# USB_OTG.net
KiCad netlist of a schematic drawn in Altium Designer
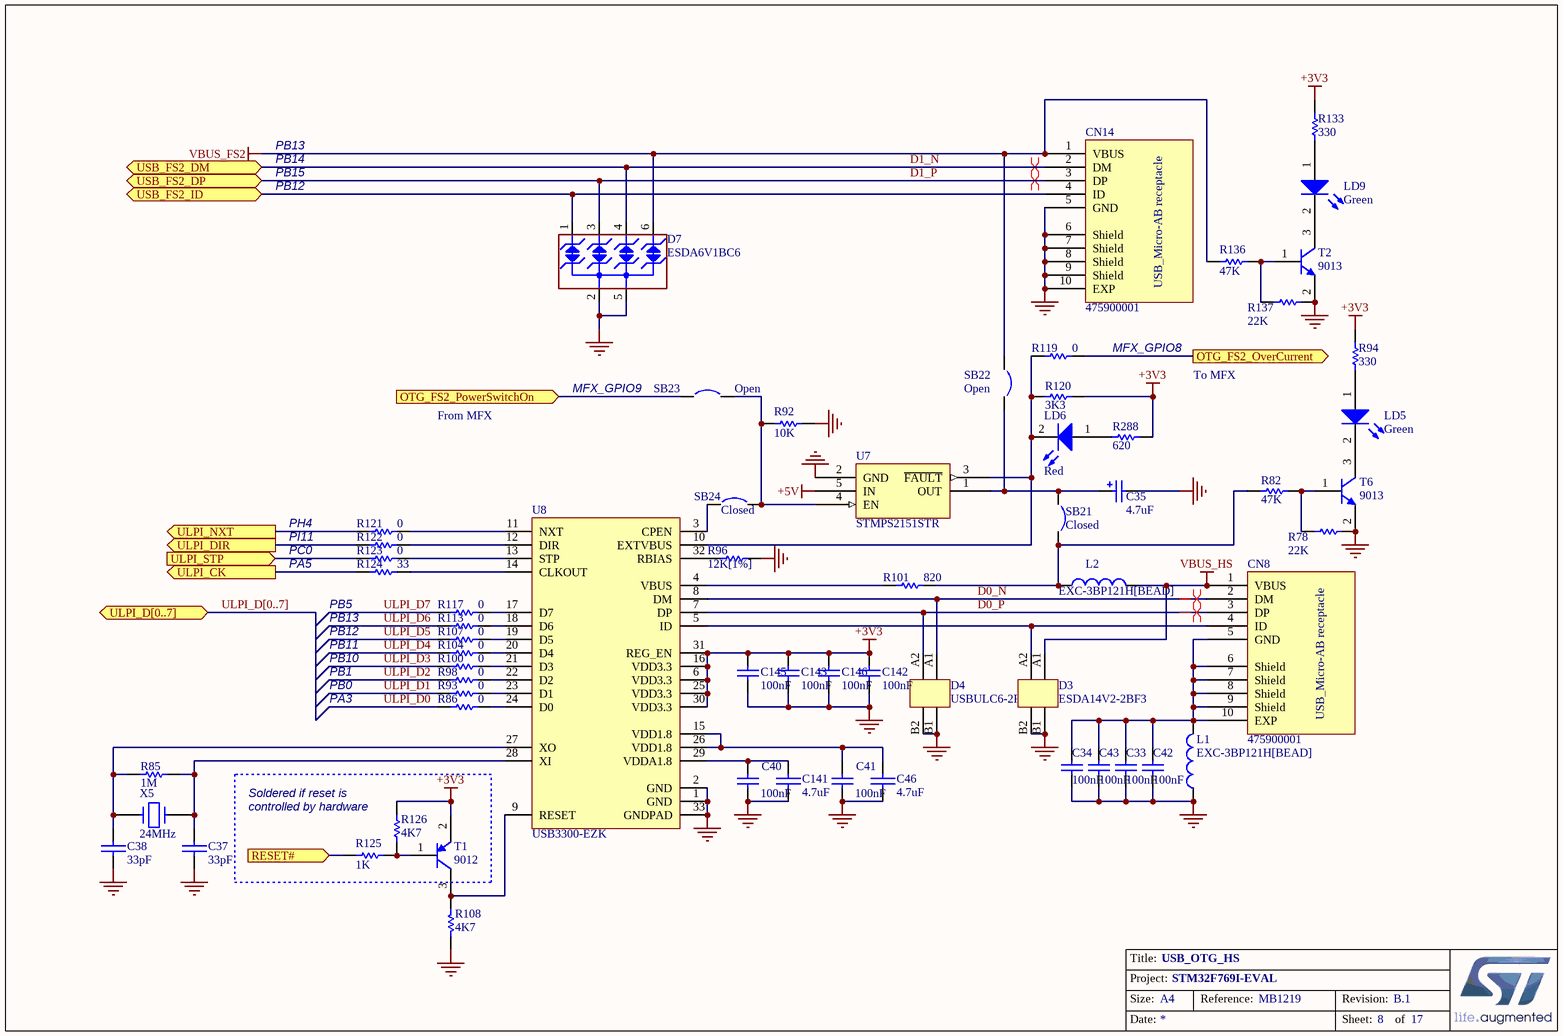
[diagram p0: USB_OTG.SchDoc]

(export (version "E")
  (design (tool "Eeschema 10.0.6"))
  (components
    (comp (ref "C33")
      (value "100nF")
      (footprint "0603C")
      (description "Capacitor")
      (fields (field (name "PUBLISHER") "Altium Limited"))
      (libsource (lib "Miscellaneous Devices") (part "Cap"))
    )
    (comp (ref "C34")
      (value "100nF")
      (footprint "0603C")
      (description "Capacitor")
      (fields (field (name "PUBLISHER") "Altium Limited"))
      (libsource (lib "Miscellaneous Devices") (part "Cap"))
    )
    (comp (ref "C35")
      (value "4.7uF")
      (footprint "TAN-A")
      (description "Polarized Capacitor (Radial)")
      (fields (field (name "PUBLISHER") "Altium Limited"))
      (libsource (lib "Miscellaneous Devices") (part "Cap Pol1"))
    )
    (comp (ref "C37")
      (value "33pF")
      (footprint "0603C")
      (description "Capacitor")
      (libsource (lib "*") (part "CAP"))
    )
    (comp (ref "C38")
      (value "33pF")
      (footprint "0603C")
      (description "Capacitor")
      (libsource (lib "*") (part "CAP"))
    )
    (comp (ref "C40")
      (value "100nF")
      (footprint "0603C")
      (description "Capacitor")
      (fields (field (name "PUBLISHER") "Altium Limited"))
      (libsource (lib "Miscellaneous Devices") (part "Cap"))
    )
    (comp (ref "C41")
      (value "100nF")
      (footprint "0603C")
      (description "Capacitor")
      (fields (field (name "PUBLISHER") "Altium Limited"))
      (libsource (lib "Miscellaneous Devices") (part "Cap"))
    )
    (comp (ref "C42")
      (value "100nF")
      (footprint "0603C")
      (description "Capacitor")
      (fields (field (name "PUBLISHER") "Altium Limited"))
      (libsource (lib "Miscellaneous Devices") (part "Cap"))
    )
    (comp (ref "C43")
      (value "100nF")
      (footprint "0603C")
      (description "Capacitor")
      (fields (field (name "PUBLISHER") "Altium Limited"))
      (libsource (lib "Miscellaneous Devices") (part "Cap"))
    )
    (comp (ref "C46")
      (value "4.7uF")
      (footprint "TAN-A")
      (description "Capacitor")
      (libsource (lib "") (part "CAP_1"))
    )
    (comp (ref "C141")
      (value "4.7uF")
      (footprint "TAN-A")
      (description "Capacitor")
      (libsource (lib "") (part "CAP_1"))
    )
    (comp (ref "C142")
      (value "100nF")
      (footprint "0603C")
      (description "Capacitor")
      (fields (field (name "PUBLISHER") "Altium Limited"))
      (libsource (lib "Miscellaneous Devices") (part "Cap"))
    )
    (comp (ref "C143")
      (value "100nF")
      (footprint "0603C")
      (description "Capacitor")
      (fields (field (name "PUBLISHER") "Altium Limited"))
      (libsource (lib "Miscellaneous Devices") (part "Cap"))
    )
    (comp (ref "C145")
      (value "100nF")
      (footprint "0603C")
      (description "Capacitor")
      (fields (field (name "PUBLISHER") "Altium Limited"))
      (libsource (lib "Miscellaneous Devices") (part "Cap"))
    )
    (comp (ref "C146")
      (value "100nF")
      (footprint "0603C")
      (description "Capacitor")
      (fields (field (name "PUBLISHER") "Altium Limited"))
      (libsource (lib "Miscellaneous Devices") (part "Cap"))
    )
    (comp (ref "CN8")
      (value "475900001")
      (footprint "MOLEX_47590001")
      (libsource (lib "mb1045") (part "475900001"))
    )
    (comp (ref "CN14")
      (value "475900001")
      (footprint "MOLEX_47590001")
      (libsource (lib "mb1045") (part "475900001"))
    )
    (comp (ref "D3")
      (value "ESDA14V2-2BF3")
      (footprint "BGA4_0R4_0R8X0R8")
      (libsource (lib "MB786") (part "ESDA14V2-2BF3"))
    )
    (comp (ref "D4")
      (value "USBULC6-2F3")
      (footprint "BGA4_0R4_1X1")
      (libsource (lib "MB786") (part "USBULC6-2F3"))
    )
    (comp (ref "D7")
      (value "ESDA6V1BC6")
      (footprint "SOT23-6")
      (description "Dual Transil array for ESD protection")
      (libsource (lib "MB1137") (part "ESDA6V1BC6"))
    )
    (comp (ref "L1")
      (value "EXC-3BP121H[BEAD]")
      (footprint "0603L")
      (description "Inductor")
      (fields (field (name "PUBLISHER") "Altium Limited"))
      (libsource (lib "Miscellaneous Devices") (part "Inductor"))
    )
    (comp (ref "L2")
      (value "EXC-3BP121H[BEAD]")
      (footprint "0603L")
      (description "Inductor")
      (fields (field (name "PUBLISHER") "Altium Limited"))
      (libsource (lib "Miscellaneous Devices") (part "Inductor"))
    )
    (comp (ref "LD5")
      (value "Green")
      (footprint "0603D")
      (description "Typical RED, GREEN, YELLOW, AMBER GaAs LED")
      (fields (field (name "PUBLISHER") "Altium Limited"))
      (libsource (lib "Miscellaneous Devices") (part "LED2"))
    )
    (comp (ref "LD6")
      (value "Red")
      (footprint "0603D")
      (description "Typical RED, GREEN, YELLOW, AMBER GaAs LED")
      (fields (field (name "PUBLISHER") "Altium Limited"))
      (libsource (lib "Miscellaneous Devices") (part "LED2"))
    )
    (comp (ref "LD9")
      (value "Green")
      (footprint "0603D")
      (description "Typical RED, GREEN, YELLOW, AMBER GaAs LED")
      (fields (field (name "PUBLISHER") "Altium Limited"))
      (libsource (lib "Miscellaneous Devices") (part "LED2"))
    )
    (comp (ref "R78")
      (value "22K")
      (footprint "0603R")
      (description "Resistor")
      (fields (field (name "PUBLISHER") "Altium Limited"))
      (libsource (lib "Miscellaneous Devices") (part "res1"))
    )
    (comp (ref "R82")
      (value "47K")
      (footprint "0603R")
      (description "Resistor")
      (fields (field (name "PUBLISHER") "Altium Limited"))
      (libsource (lib "Miscellaneous Devices") (part "res1"))
    )
    (comp (ref "R85")
      (value "1M")
      (footprint "0603R")
      (description "Resistor")
      (fields (field (name "PUBLISHER") "Altium Limited"))
      (libsource (lib "Miscellaneous Devices") (part "Res1"))
    )
    (comp (ref "R86")
      (value "0")
      (footprint "0603R")
      (description "Resistor")
      (fields (field (name "PUBLISHER") "Altium Limited"))
      (libsource (lib "Miscellaneous Devices") (part "Res1"))
    )
    (comp (ref "R92")
      (value "10K")
      (footprint "0603R")
      (description "Resistor")
      (fields (field (name "PUBLISHER") "Altium Limited"))
      (libsource (lib "Miscellaneous Devices") (part "res1"))
    )
    (comp (ref "R93")
      (value "0")
      (footprint "0603R")
      (description "Resistor")
      (fields (field (name "PUBLISHER") "Altium Limited"))
      (libsource (lib "Miscellaneous Devices") (part "Res1"))
    )
    (comp (ref "R94")
      (value "330")
      (footprint "0603R")
      (description "Resistor")
      (fields (field (name "PUBLISHER") "Altium Limited"))
      (libsource (lib "Miscellaneous Devices") (part "res1"))
    )
    (comp (ref "R96")
      (value "12K[1%]")
      (footprint "0603R")
      (description "Resistor")
      (fields (field (name "PUBLISHER") "Altium Limited"))
      (libsource (lib "Miscellaneous Devices") (part "Res1"))
    )
    (comp (ref "R98")
      (value "0")
      (footprint "0603R")
      (description "Resistor")
      (fields (field (name "PUBLISHER") "Altium Limited"))
      (libsource (lib "Miscellaneous Devices") (part "Res1"))
    )
    (comp (ref "R100")
      (value "0")
      (footprint "0603R")
      (description "Resistor")
      (fields (field (name "PUBLISHER") "Altium Limited"))
      (libsource (lib "Miscellaneous Devices") (part "Res1"))
    )
    (comp (ref "R101")
      (value "820")
      (footprint "0603R")
      (description "Resistor")
      (fields (field (name "PUBLISHER") "Altium Limited"))
      (libsource (lib "Miscellaneous Devices") (part "res1"))
    )
    (comp (ref "R104")
      (value "0")
      (footprint "0603R")
      (description "Resistor")
      (fields (field (name "PUBLISHER") "Altium Limited"))
      (libsource (lib "Miscellaneous Devices") (part "Res1"))
    )
    (comp (ref "R107")
      (value "0")
      (footprint "0603R")
      (description "Resistor")
      (fields (field (name "PUBLISHER") "Altium Limited"))
      (libsource (lib "Miscellaneous Devices") (part "Res1"))
    )
    (comp (ref "R108")
      (value "4K7")
      (footprint "0603R")
      (description "Resistor")
      (fields (field (name "PUBLISHER") "Altium Limited"))
      (libsource (lib "*") (part "Res1"))
    )
    (comp (ref "R113")
      (value "0")
      (footprint "0603R")
      (description "Resistor")
      (fields (field (name "PUBLISHER") "Altium Limited"))
      (libsource (lib "Miscellaneous Devices") (part "Res1"))
    )
    (comp (ref "R117")
      (value "0")
      (footprint "0603R")
      (description "Resistor")
      (fields (field (name "PUBLISHER") "Altium Limited"))
      (libsource (lib "Miscellaneous Devices") (part "Res1"))
    )
    (comp (ref "R119")
      (value "0")
      (footprint "0603R")
      (description "Resistor")
      (fields (field (name "PUBLISHER") "Altium Limited"))
      (libsource (lib "Miscellaneous Devices") (part "Res1"))
    )
    (comp (ref "R120")
      (value "3K3")
      (footprint "0603R")
      (description "Resistor")
      (fields (field (name "PUBLISHER") "Altium Limited"))
      (libsource (lib "Miscellaneous Devices") (part "res1"))
    )
    (comp (ref "R121")
      (value "0")
      (footprint "0603R")
      (description "Resistor")
      (fields (field (name "PUBLISHER") "Altium Limited"))
      (libsource (lib "Miscellaneous Devices") (part "Res1"))
    )
    (comp (ref "R122")
      (value "0")
      (footprint "0603R")
      (description "Resistor")
      (fields (field (name "PUBLISHER") "Altium Limited"))
      (libsource (lib "Miscellaneous Devices") (part "Res1"))
    )
    (comp (ref "R123")
      (value "0")
      (footprint "0603R")
      (description "Resistor")
      (fields (field (name "PUBLISHER") "Altium Limited"))
      (libsource (lib "Miscellaneous Devices") (part "Res1"))
    )
    (comp (ref "R124")
      (value "33")
      (footprint "0603R")
      (description "Resistor")
      (fields (field (name "PUBLISHER") "Altium Limited"))
      (libsource (lib "Miscellaneous Devices") (part "Res1"))
    )
    (comp (ref "R125")
      (value "1K")
      (footprint "0603R")
      (description "Resistor")
      (fields (field (name "PUBLISHER") "Altium Limited"))
      (libsource (lib "Miscellaneous Devices") (part "Res1"))
    )
    (comp (ref "R126")
      (value "4K7")
      (footprint "0603R")
      (description "Resistor")
      (fields (field (name "PUBLISHER") "Altium Limited"))
      (libsource (lib "*") (part "Res1"))
    )
    (comp (ref "R133")
      (value "330")
      (footprint "0603R")
      (description "Resistor")
      (fields (field (name "PUBLISHER") "Altium Limited"))
      (libsource (lib "Miscellaneous Devices") (part "res1"))
    )
    (comp (ref "R136")
      (value "47K")
      (footprint "0603R")
      (description "Resistor")
      (fields (field (name "PUBLISHER") "Altium Limited"))
      (libsource (lib "Miscellaneous Devices") (part "res1"))
    )
    (comp (ref "R137")
      (value "22K")
      (footprint "0603R")
      (description "Resistor")
      (fields (field (name "PUBLISHER") "Altium Limited"))
      (libsource (lib "Miscellaneous Devices") (part "res1"))
    )
    (comp (ref "R288")
      (value "620")
      (footprint "0603R")
      (description "Resistor")
      (fields (field (name "PUBLISHER") "Altium Limited"))
      (libsource (lib "Miscellaneous Devices") (part "Res1"))
    )
    (comp (ref "SB21")
      (value "Closed")
      (footprint "SB_0603")
      (description "Circuit Breaker")
      (fields (field (name "PUBLISHER") "Altium Limited"))
      (libsource (lib "MB1167") (part "Circuit Breaker_close"))
    )
    (comp (ref "SB22")
      (value "Open")
      (footprint "SB_0603")
      (description "Circuit Breaker")
      (fields (field (name "PUBLISHER") "Altium Limited"))
      (libsource (lib "MB1167") (part "Circuit Breaker"))
    )
    (comp (ref "SB23")
      (value "Open")
      (footprint "SB_0603")
      (description "Circuit Breaker")
      (fields (field (name "PUBLISHER") "Altium Limited"))
      (libsource (lib "MB1167") (part "Circuit Breaker"))
    )
    (comp (ref "SB24")
      (value "Closed")
      (footprint "SB_0603")
      (description "Circuit Breaker")
      (fields (field (name "PUBLISHER") "Altium Limited"))
      (libsource (lib "MB1167") (part "Circuit Breaker_close"))
    )
    (comp (ref "T1")
      (value "9012")
      (footprint "SOT-23")
      (description "PNP Bipolar Transistor")
      (fields (field (name "PUBLISHER") "Altium Limited"))
      (libsource (lib "MB1167") (part "PNP"))
    )
    (comp (ref "T2")
      (value "9013")
      (footprint "SOT-23")
      (description "NPN Bipolar Transistor")
      (fields (field (name "PUBLISHER") "Altium Limited"))
      (libsource (lib "MB1167") (part "NPN"))
    )
    (comp (ref "T6")
      (value "9013")
      (footprint "SOT-23")
      (description "NPN Bipolar Transistor")
      (fields (field (name "PUBLISHER") "Altium Limited"))
      (libsource (lib "MB1167") (part "NPN"))
    )
    (comp (ref "U7")
      (value "STMPS2151STR")
      (footprint "SOT23-5")
      (libsource (lib "mb1045") (part "STMPS2141STR"))
    )
    (comp (ref "U8")
      (value "USB3300-EZK")
      (footprint "QFN32_0R5_5X5")
      (libsource (lib "MB1000_1") (part "USB3300-EZK"))
    )
    (comp (ref "X5")
      (value "24MHz")
      (footprint "XTAL1")
      (description "Crystal")
      (libsource (lib "*") (part "CRYSTAL"))
    )
  )
  (nets
    (net (code "1") (name "+3V3") (class "Default")
      (node (ref "C142") (pin "1") (pinfunction "1_1") (pintype "passive"))
      (node (ref "C143") (pin "1") (pinfunction "1_1") (pintype "passive"))
      (node (ref "C145") (pin "1") (pinfunction "1_1") (pintype "passive"))
      (node (ref "C146") (pin "1") (pinfunction "1_1") (pintype "passive"))
      (node (ref "R120") (pin "1") (pinfunction "1_1") (pintype "passive"))
      (node (ref "R126") (pin "1") (pinfunction "1_1") (pintype "passive"))
      (node (ref "R133") (pin "2") (pinfunction "2_2") (pintype "passive"))
      (node (ref "R288") (pin "2") (pinfunction "2_2") (pintype "passive"))
      (node (ref "R94") (pin "2") (pinfunction "2_2") (pintype "passive"))
      (node (ref "T1") (pin "2") (pinfunction "E_2") (pintype "passive"))
      (node (ref "U8") (pin "16") (pinfunction "VDD3.3_16") (pintype "passive"))
      (node (ref "U8") (pin "25") (pinfunction "VDD3.3_25") (pintype "passive"))
      (node (ref "U8") (pin "30") (pinfunction "VDD3.3_30") (pintype "passive"))
      (node (ref "U8") (pin "31") (pinfunction "REG_EN_31") (pintype "passive"))
      (node (ref "U8") (pin "6") (pinfunction "VDD3.3_6") (pintype "passive"))
    )
    (net (code "2") (name "+5V") (class "Default")
      (node (ref "U7") (pin "5") (pinfunction "IN_5") (pintype "passive"))
    )
    (net (code "3") (name "/D0_N") (class "Default")
      (node (ref "CN8") (pin "2") (pinfunction "DM_2") (pintype "passive"))
      (node (ref "D4") (pin "A1") (pintype "passive"))
      (node (ref "U8") (pin "8") (pinfunction "DM_8") (pintype "passive"))
    )
    (net (code "4") (name "/D0_P") (class "Default")
      (node (ref "CN8") (pin "3") (pinfunction "DP_3") (pintype "passive"))
      (node (ref "D4") (pin "A2") (pintype "passive"))
      (node (ref "U8") (pin "7") (pinfunction "DP_7") (pintype "passive"))
    )
    (net (code "5") (name "/D1_N") (class "Default")
      (node (ref "CN14") (pin "2") (pinfunction "DM_2") (pintype "passive"))
      (node (ref "D7") (pin "4") (pinfunction "IO3_4") (pintype "passive"))
    )
    (net (code "6") (name "/D1_P") (class "Default")
      (node (ref "CN14") (pin "3") (pinfunction "DP_3") (pintype "passive"))
      (node (ref "D7") (pin "3") (pinfunction "GND_3") (pintype "passive"))
    )
    (net (code "7") (name "/OTG_FS2_OverCurrent") (class "Default")
      (node (ref "R119") (pin "1") (pinfunction "1_1") (pintype "passive"))
    )
    (net (code "8") (name "/OTG_FS2_PowerSwitchOn") (class "Default")
      (node (ref "SB23") (pin "1") (pinfunction "1_1") (pintype "passive"))
    )
    (net (code "9") (name "/RESET#") (class "Default")
      (node (ref "R125") (pin "2") (pinfunction "2_2") (pintype "passive"))
    )
    (net (code "10") (name "/ULPI_CK") (class "Default")
      (node (ref "R124") (pin "2") (pinfunction "2_2") (pintype "passive"))
    )
    (net (code "11") (name "/ULPI_D0") (class "Default")
      (node (ref "R86") (pin "2") (pinfunction "2_2") (pintype "passive"))
    )
    (net (code "12") (name "/ULPI_D1") (class "Default")
      (node (ref "R93") (pin "2") (pinfunction "2_2") (pintype "passive"))
    )
    (net (code "13") (name "/ULPI_D2") (class "Default")
      (node (ref "R98") (pin "2") (pinfunction "2_2") (pintype "passive"))
    )
    (net (code "14") (name "/ULPI_D3") (class "Default")
      (node (ref "R100") (pin "2") (pinfunction "2_2") (pintype "passive"))
    )
    (net (code "15") (name "/ULPI_D4") (class "Default")
      (node (ref "R104") (pin "2") (pinfunction "2_2") (pintype "passive"))
    )
    (net (code "16") (name "/ULPI_D5") (class "Default")
      (node (ref "R107") (pin "2") (pinfunction "2_2") (pintype "passive"))
    )
    (net (code "17") (name "/ULPI_D6") (class "Default")
      (node (ref "R113") (pin "2") (pinfunction "2_2") (pintype "passive"))
    )
    (net (code "18") (name "/ULPI_D7") (class "Default")
      (node (ref "R117") (pin "2") (pinfunction "2_2") (pintype "passive"))
    )
    (net (code "19") (name "/ULPI_DIR") (class "Default")
      (node (ref "R122") (pin "2") (pinfunction "2_2") (pintype "passive"))
    )
    (net (code "21") (name "/ULPI_NXT") (class "Default")
      (node (ref "R121") (pin "2") (pinfunction "2_2") (pintype "passive"))
    )
    (net (code "22") (name "/ULPI_STP") (class "Default")
      (node (ref "R123") (pin "2") (pinfunction "2_2") (pintype "passive"))
    )
    (net (code "23") (name "/USB_FS2_ID") (class "Default")
      (node (ref "CN14") (pin "4") (pinfunction "ID_4") (pintype "passive"))
      (node (ref "D7") (pin "1") (pinfunction "IO1_1") (pintype "passive"))
    )
    (net (code "24") (name "GND") (class "Default")
      (node (ref "C141") (pin "2") (pinfunction "2_2") (pintype "passive"))
      (node (ref "C142") (pin "2") (pinfunction "2_2") (pintype "passive"))
      (node (ref "C143") (pin "2") (pinfunction "2_2") (pintype "passive"))
      (node (ref "C145") (pin "2") (pinfunction "2_2") (pintype "passive"))
      (node (ref "C146") (pin "2") (pinfunction "2_2") (pintype "passive"))
      (node (ref "C33") (pin "2") (pinfunction "2_2") (pintype "passive"))
      (node (ref "C34") (pin "2") (pinfunction "2_2") (pintype "passive"))
      (node (ref "C35") (pin "2") (pinfunction "2_2") (pintype "passive"))
      (node (ref "C37") (pin "2") (pinfunction "2_2") (pintype "passive"))
      (node (ref "C38") (pin "2") (pinfunction "2_2") (pintype "passive"))
      (node (ref "C40") (pin "2") (pinfunction "2_2") (pintype "passive"))
      (node (ref "C41") (pin "2") (pinfunction "2_2") (pintype "passive"))
      (node (ref "C42") (pin "2") (pinfunction "2_2") (pintype "passive"))
      (node (ref "C43") (pin "2") (pinfunction "2_2") (pintype "passive"))
      (node (ref "C46") (pin "2") (pinfunction "2_2") (pintype "passive"))
      (node (ref "CN14") (pin "10") (pinfunction "EXP_10") (pintype "passive"))
      (node (ref "CN14") (pin "5") (pinfunction "GND_5") (pintype "passive"))
      (node (ref "CN14") (pin "6") (pinfunction "Shield_6") (pintype "passive"))
      (node (ref "CN14") (pin "7") (pinfunction "Shield_7") (pintype "passive"))
      (node (ref "CN14") (pin "8") (pinfunction "Shield_8") (pintype "passive"))
      (node (ref "CN14") (pin "9") (pinfunction "Shield_9") (pintype "passive"))
      (node (ref "D3") (pin "B1") (pintype "passive"))
      (node (ref "D3") (pin "B2") (pintype "passive"))
      (node (ref "D4") (pin "B1") (pintype "passive"))
      (node (ref "D4") (pin "B2") (pintype "passive"))
      (node (ref "D7") (pin "2") (pinfunction "IO2_2") (pintype "passive"))
      (node (ref "D7") (pin "5") (pinfunction "IO4_5") (pintype "passive"))
      (node (ref "L1") (pin "1") (pinfunction "1_1") (pintype "passive"))
      (node (ref "R108") (pin "1") (pinfunction "1_1") (pintype "passive"))
      (node (ref "R137") (pin "1") (pinfunction "1_1") (pintype "passive"))
      (node (ref "R78") (pin "1") (pinfunction "1_1") (pintype "passive"))
      (node (ref "R92") (pin "1") (pinfunction "1_1") (pintype "passive"))
      (node (ref "R96") (pin "1") (pinfunction "1_1") (pintype "passive"))
      (node (ref "T2") (pin "2") (pinfunction "E_2") (pintype "passive"))
      (node (ref "T6") (pin "2") (pinfunction "E_2") (pintype "passive"))
      (node (ref "U7") (pin "2") (pinfunction "GND_2") (pintype "passive"))
      (node (ref "U8") (pin "1") (pinfunction "GND_1") (pintype "passive"))
      (node (ref "U8") (pin "2") (pinfunction "GND_2") (pintype "passive"))
      (node (ref "U8") (pin "33") (pinfunction "GNDPAD_33") (pintype "passive"))
    )
    (net (code "25") (name "Net-(C41-Pad1)") (class "Default")
      (node (ref "C41") (pin "1") (pinfunction "1_1") (pintype "passive"))
      (node (ref "C46") (pin "1") (pinfunction "1_1") (pintype "passive"))
      (node (ref "U8") (pin "15") (pinfunction "VDD1.8_15") (pintype "passive"))
      (node (ref "U8") (pin "26") (pinfunction "VDD1.8_26") (pintype "passive"))
    )
    (net (code "26") (name "Net-(CN8-EXP)") (class "Default")
      (node (ref "C33") (pin "1") (pinfunction "1_1") (pintype "passive"))
      (node (ref "C34") (pin "1") (pinfunction "1_1") (pintype "passive"))
      (node (ref "C42") (pin "1") (pinfunction "1_1") (pintype "passive"))
      (node (ref "C43") (pin "1") (pinfunction "1_1") (pintype "passive"))
      (node (ref "CN8") (pin "10") (pinfunction "EXP_10") (pintype "passive"))
      (node (ref "CN8") (pin "5") (pinfunction "GND_5") (pintype "passive"))
      (node (ref "CN8") (pin "6") (pinfunction "Shield_6") (pintype "passive"))
      (node (ref "CN8") (pin "7") (pinfunction "Shield_7") (pintype "passive"))
      (node (ref "CN8") (pin "8") (pinfunction "Shield_8") (pintype "passive"))
      (node (ref "CN8") (pin "9") (pinfunction "Shield_9") (pintype "passive"))
      (node (ref "L1") (pin "2") (pinfunction "2_2") (pintype "passive"))
    )
    (net (code "27") (name "Net-(CN8-ID)") (class "Default")
      (node (ref "CN8") (pin "4") (pinfunction "ID_4") (pintype "passive"))
      (node (ref "D3") (pin "A2") (pintype "passive"))
      (node (ref "U8") (pin "5") (pinfunction "ID_5") (pintype "passive"))
    )
    (net (code "28") (name "Net-(L2-Pad1)") (class "Default")
      (node (ref "L2") (pin "1") (pinfunction "1_1") (pintype "passive"))
      (node (ref "R101") (pin "2") (pinfunction "2_2") (pintype "passive"))
      (node (ref "R82") (pin "2") (pinfunction "2_2") (pintype "passive"))
      (node (ref "SB21") (pin "2") (pinfunction "2_2") (pintype "passive"))
    )
    (net (code "29") (name "Net-(LD5-A)") (class "Default")
      (node (ref "LD5") (pin "1") (pinfunction "A_1") (pintype "passive"))
      (node (ref "R94") (pin "1") (pinfunction "1_1") (pintype "passive"))
    )
    (net (code "30") (name "Net-(LD5-K)") (class "Default")
      (node (ref "LD5") (pin "2") (pinfunction "K_2") (pintype "passive"))
      (node (ref "T6") (pin "3") (pinfunction "C_3") (pintype "passive"))
    )
    (net (code "31") (name "Net-(LD6-A)") (class "Default")
      (node (ref "LD6") (pin "1") (pinfunction "A_1") (pintype "passive"))
      (node (ref "R288") (pin "1") (pinfunction "1_1") (pintype "passive"))
    )
    (net (code "32") (name "Net-(LD6-K)") (class "Default")
      (node (ref "LD6") (pin "2") (pinfunction "K_2") (pintype "passive"))
      (node (ref "R119") (pin "2") (pinfunction "2_2") (pintype "passive"))
      (node (ref "R120") (pin "2") (pinfunction "2_2") (pintype "passive"))
      (node (ref "U7") (pin "3") (pinfunction "~{FAULT}_3") (pintype "output"))
      (node (ref "U8") (pin "10") (pinfunction "EXTVBUS_10") (pintype "passive"))
    )
    (net (code "33") (name "Net-(LD9-A)") (class "Default")
      (node (ref "LD9") (pin "1") (pinfunction "A_1") (pintype "passive"))
      (node (ref "R133") (pin "1") (pinfunction "1_1") (pintype "passive"))
    )
    (net (code "34") (name "Net-(LD9-K)") (class "Default")
      (node (ref "LD9") (pin "2") (pinfunction "K_2") (pintype "passive"))
      (node (ref "T2") (pin "3") (pinfunction "C_3") (pintype "passive"))
    )
    (net (code "35") (name "Net-(T1-B)") (class "Default")
      (node (ref "R125") (pin "1") (pinfunction "1_1") (pintype "passive"))
      (node (ref "R126") (pin "2") (pinfunction "2_2") (pintype "passive"))
      (node (ref "T1") (pin "1") (pinfunction "B_1") (pintype "passive"))
    )
    (net (code "36") (name "Net-(T1-C)") (class "Default")
      (node (ref "R108") (pin "2") (pinfunction "2_2") (pintype "passive"))
      (node (ref "T1") (pin "3") (pinfunction "C_3") (pintype "passive"))
      (node (ref "U8") (pin "9") (pinfunction "RESET_9") (pintype "passive"))
    )
    (net (code "37") (name "Net-(T2-B)") (class "Default")
      (node (ref "R136") (pin "2") (pinfunction "2_2") (pintype "passive"))
      (node (ref "R137") (pin "2") (pinfunction "2_2") (pintype "passive"))
      (node (ref "T2") (pin "1") (pinfunction "B_1") (pintype "passive"))
    )
    (net (code "38") (name "Net-(T6-B)") (class "Default")
      (node (ref "R78") (pin "2") (pinfunction "2_2") (pintype "passive"))
      (node (ref "R82") (pin "1") (pinfunction "1_1") (pintype "passive"))
      (node (ref "T6") (pin "1") (pinfunction "B_1") (pintype "passive"))
    )
    (net (code "39") (name "Net-(U7-EN)") (class "Default")
      (node (ref "R92") (pin "2") (pinfunction "2_2") (pintype "passive"))
      (node (ref "SB23") (pin "2") (pinfunction "2_2") (pintype "passive"))
      (node (ref "SB24") (pin "2") (pinfunction "2_2") (pintype "passive"))
      (node (ref "U7") (pin "4") (pinfunction "EN_4") (pintype "input"))
    )
    (net (code "40") (name "Net-(U7-OUT)") (class "Default")
      (node (ref "C35") (pin "1") (pinfunction "1_1") (pintype "passive"))
      (node (ref "SB21") (pin "1") (pinfunction "1_1") (pintype "passive"))
      (node (ref "SB22") (pin "2") (pinfunction "2_2") (pintype "passive"))
      (node (ref "U7") (pin "1") (pinfunction "OUT_1") (pintype "passive"))
    )
    (net (code "41") (name "Net-(U8-CLKOUT)") (class "Default")
      (node (ref "R124") (pin "1") (pinfunction "1_1") (pintype "passive"))
      (node (ref "U8") (pin "14") (pinfunction "CLKOUT_14") (pintype "passive"))
    )
    (net (code "42") (name "Net-(U8-CPEN)") (class "Default")
      (node (ref "SB24") (pin "1") (pinfunction "1_1") (pintype "passive"))
      (node (ref "U8") (pin "3") (pinfunction "CPEN_3") (pintype "passive"))
    )
    (net (code "43") (name "Net-(U8-D0)") (class "Default")
      (node (ref "R86") (pin "1") (pinfunction "1_1") (pintype "passive"))
      (node (ref "U8") (pin "24") (pinfunction "D0_24") (pintype "passive"))
    )
    (net (code "44") (name "Net-(U8-D1)") (class "Default")
      (node (ref "R93") (pin "1") (pinfunction "1_1") (pintype "passive"))
      (node (ref "U8") (pin "23") (pinfunction "D1_23") (pintype "passive"))
    )
    (net (code "45") (name "Net-(U8-D2)") (class "Default")
      (node (ref "R98") (pin "1") (pinfunction "1_1") (pintype "passive"))
      (node (ref "U8") (pin "22") (pinfunction "D2_22") (pintype "passive"))
    )
    (net (code "46") (name "Net-(U8-D3)") (class "Default")
      (node (ref "R100") (pin "1") (pinfunction "1_1") (pintype "passive"))
      (node (ref "U8") (pin "21") (pinfunction "D3_21") (pintype "passive"))
    )
    (net (code "47") (name "Net-(U8-D4)") (class "Default")
      (node (ref "R104") (pin "1") (pinfunction "1_1") (pintype "passive"))
      (node (ref "U8") (pin "20") (pinfunction "D4_20") (pintype "passive"))
    )
    (net (code "48") (name "Net-(U8-D5)") (class "Default")
      (node (ref "R107") (pin "1") (pinfunction "1_1") (pintype "passive"))
      (node (ref "U8") (pin "19") (pinfunction "D5_19") (pintype "passive"))
    )
    (net (code "49") (name "Net-(U8-D6)") (class "Default")
      (node (ref "R113") (pin "1") (pinfunction "1_1") (pintype "passive"))
      (node (ref "U8") (pin "18") (pinfunction "D6_18") (pintype "passive"))
    )
    (net (code "50") (name "Net-(U8-D7)") (class "Default")
      (node (ref "R117") (pin "1") (pinfunction "1_1") (pintype "passive"))
      (node (ref "U8") (pin "17") (pinfunction "D7_17") (pintype "passive"))
    )
    (net (code "51") (name "Net-(U8-DIR)") (class "Default")
      (node (ref "R122") (pin "1") (pinfunction "1_1") (pintype "passive"))
      (node (ref "U8") (pin "12") (pinfunction "DIR_12") (pintype "passive"))
    )
    (net (code "52") (name "Net-(U8-NXT)") (class "Default")
      (node (ref "R121") (pin "1") (pinfunction "1_1") (pintype "passive"))
      (node (ref "U8") (pin "11") (pinfunction "NXT_11") (pintype "passive"))
    )
    (net (code "53") (name "Net-(U8-RBIAS)") (class "Default")
      (node (ref "R96") (pin "2") (pinfunction "2_2") (pintype "passive"))
      (node (ref "U8") (pin "32") (pinfunction "RBIAS_32") (pintype "passive"))
    )
    (net (code "54") (name "Net-(U8-STP)") (class "Default")
      (node (ref "R123") (pin "1") (pinfunction "1_1") (pintype "passive"))
      (node (ref "U8") (pin "13") (pinfunction "STP_13") (pintype "passive"))
    )
    (net (code "55") (name "Net-(U8-VBUS)") (class "Default")
      (node (ref "R101") (pin "1") (pinfunction "1_1") (pintype "passive"))
      (node (ref "U8") (pin "4") (pinfunction "VBUS_4") (pintype "passive"))
    )
    (net (code "56") (name "Net-(U8-VDDA1.8)") (class "Default")
      (node (ref "C141") (pin "1") (pinfunction "1_1") (pintype "passive"))
      (node (ref "C40") (pin "1") (pinfunction "1_1") (pintype "passive"))
      (node (ref "U8") (pin "29") (pinfunction "VDDA1.8_29") (pintype "passive"))
    )
    (net (code "57") (name "Net-(U8-XI)") (class "Default")
      (node (ref "C37") (pin "1") (pinfunction "1_1") (pintype "passive"))
      (node (ref "R85") (pin "2") (pinfunction "2_2") (pintype "passive"))
      (node (ref "U8") (pin "28") (pinfunction "XI_28") (pintype "passive"))
      (node (ref "X5") (pin "1") (pinfunction "1_1") (pintype "passive"))
    )
    (net (code "58") (name "Net-(U8-XO)") (class "Default")
      (node (ref "C38") (pin "1") (pinfunction "1_1") (pintype "passive"))
      (node (ref "R85") (pin "1") (pinfunction "1_1") (pintype "passive"))
      (node (ref "U8") (pin "27") (pinfunction "XO_27") (pintype "passive"))
      (node (ref "X5") (pin "2") (pinfunction "2_2") (pintype "passive"))
    )
    (net (code "59") (name "VBUS_FS2") (class "Default")
      (node (ref "CN14") (pin "1") (pinfunction "VBUS_1") (pintype "passive"))
      (node (ref "D7") (pin "6") (pinfunction "NC_6") (pintype "passive"))
      (node (ref "R136") (pin "1") (pinfunction "1_1") (pintype "passive"))
      (node (ref "SB22") (pin "1") (pinfunction "1_1") (pintype "passive"))
    )
    (net (code "60") (name "VBUS_HS") (class "Default")
      (node (ref "CN8") (pin "1") (pinfunction "VBUS_1") (pintype "passive"))
      (node (ref "D3") (pin "A1") (pintype "passive"))
      (node (ref "L2") (pin "2") (pinfunction "2_2") (pintype "passive"))
    )
  )
)
